# AntennaPCB_EXTV1.net
KiCad netlist of a schematic drawn in EAGLE
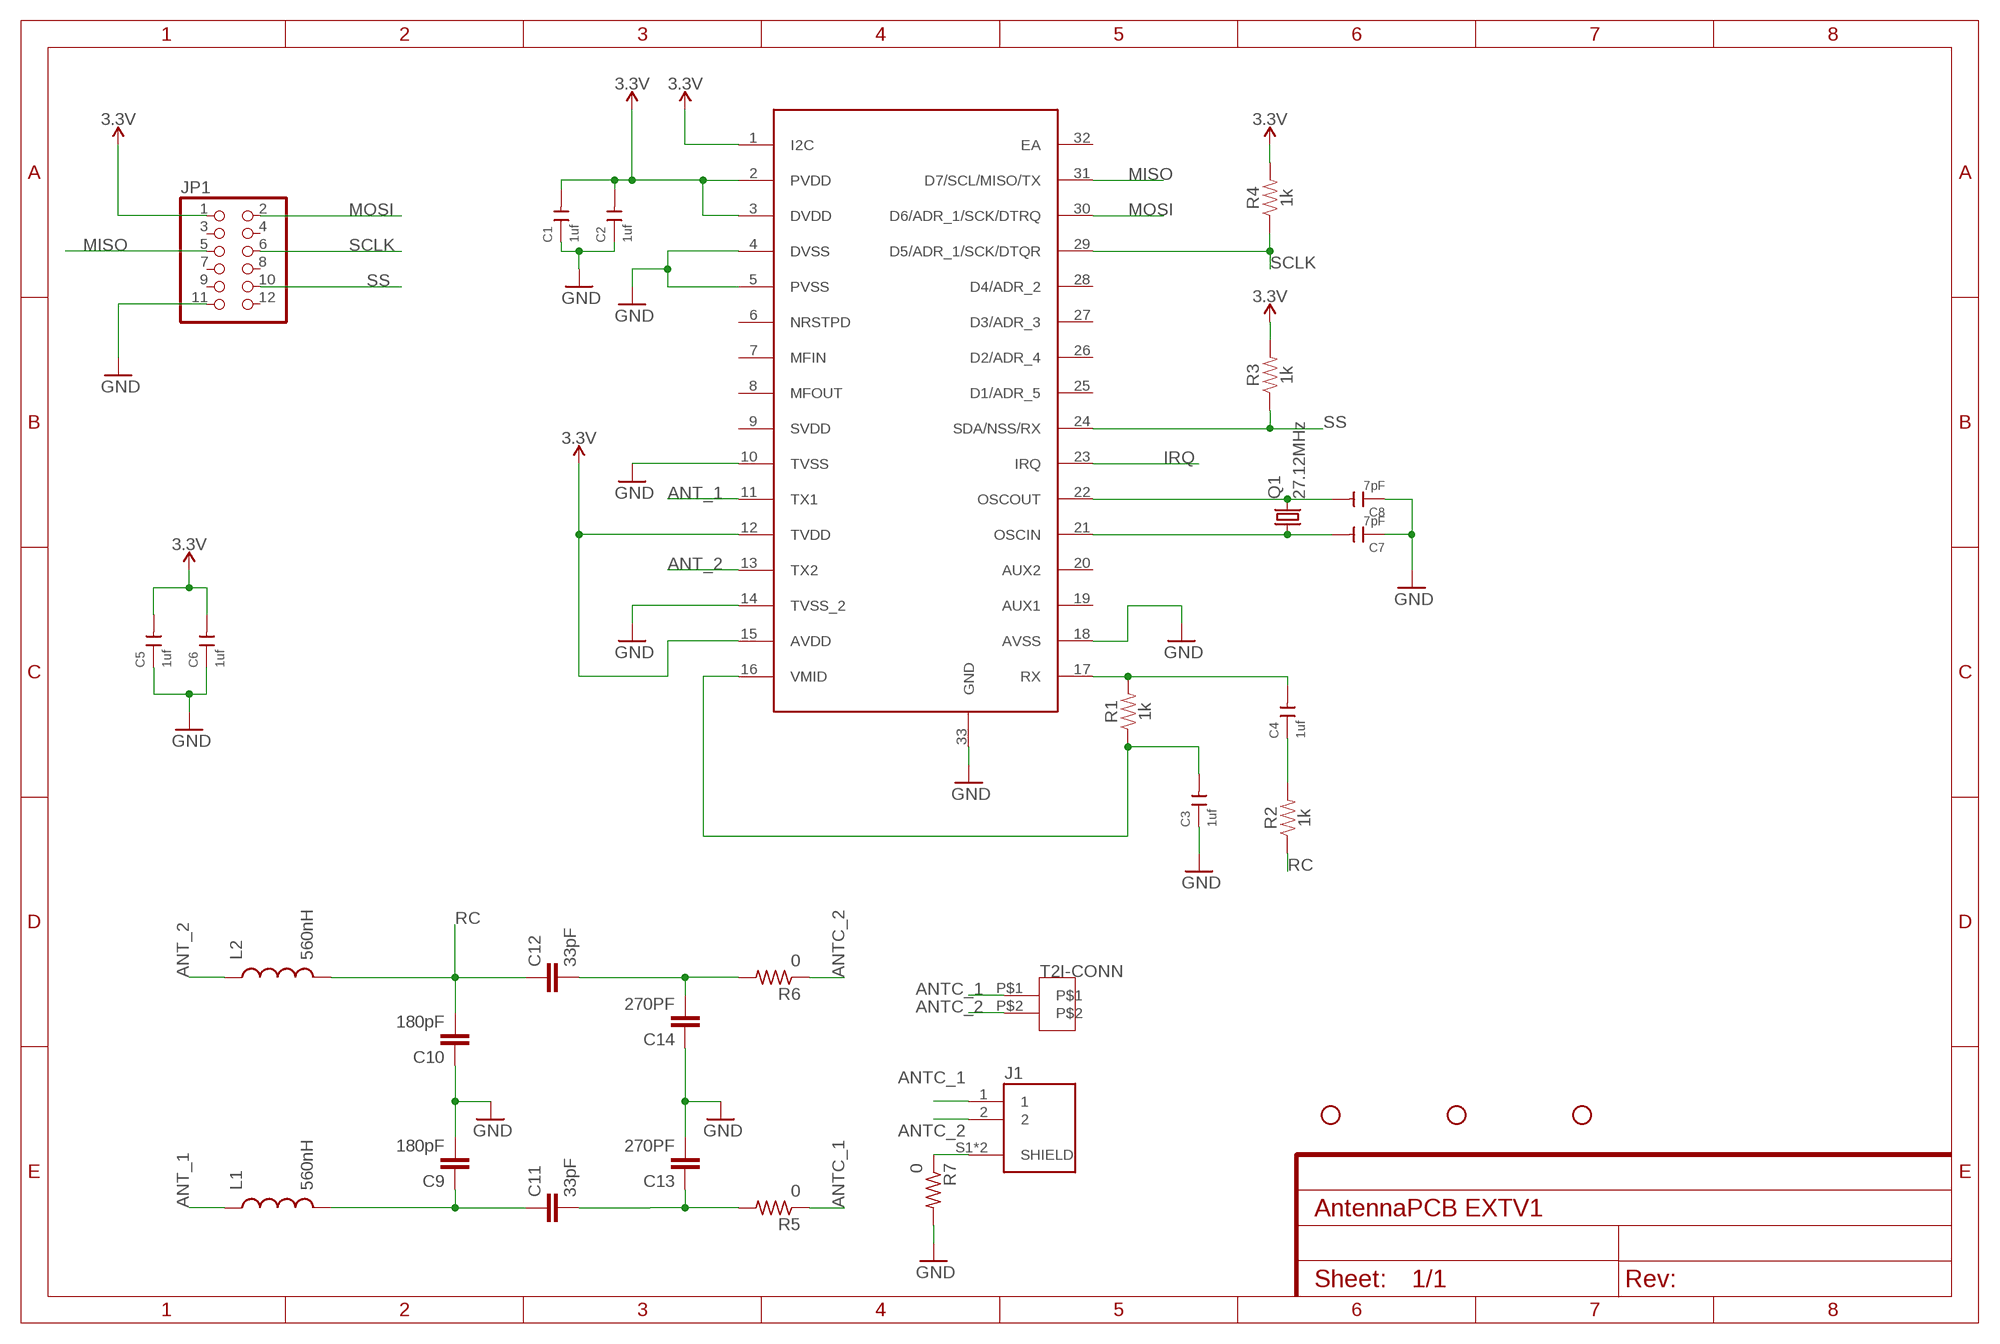
[diagram p0: schematic, sheet 1]

(export (version "E")
  (design (tool "Eeschema 10.0.6"))
  (components
    (comp (ref "C1")
      (value "1uf")
      (footprint "eagle-import:C0603")
      (fields (field (name "MPN") "CC0603KRX7R8BB105"))
      (libsource (lib "eagle-import") (part "CERAMIC-1UF-25V-10%-X7R(0603)"))
    )
    (comp (ref "C2")
      (value "1uf")
      (footprint "eagle-import:C0603")
      (fields (field (name "MPN") "CC0603KRX7R8BB105"))
      (libsource (lib "eagle-import") (part "CERAMIC-1UF-25V-10%-X7R(0603)"))
    )
    (comp (ref "C3")
      (value "1uf")
      (footprint "eagle-import:C0603")
      (fields (field (name "MPN") "CC0603KRX7R8BB105"))
      (libsource (lib "eagle-import") (part "CERAMIC-1UF-25V-10%-X7R(0603)"))
    )
    (comp (ref "C4")
      (value "1uf")
      (footprint "eagle-import:C0603")
      (fields (field (name "MPN") "CC0603KRX7R8BB105"))
      (libsource (lib "eagle-import") (part "CERAMIC-1UF-25V-10%-X7R(0603)"))
    )
    (comp (ref "C5")
      (value "1uf")
      (footprint "eagle-import:C0603")
      (fields (field (name "MPN") "CC0603KRX7R8BB105"))
      (libsource (lib "eagle-import") (part "CERAMIC-1UF-25V-10%-X7R(0603)"))
    )
    (comp (ref "C6")
      (value "1uf")
      (footprint "eagle-import:C0603")
      (fields (field (name "MPN") "CC0603KRX7R8BB105"))
      (libsource (lib "eagle-import") (part "CERAMIC-1UF-25V-10%-X7R(0603)"))
    )
    (comp (ref "C7")
      (value "7pF")
      (footprint "eagle-import:C0603")
      (fields (field (name "MPN") "CC0603KRX7R8BB105"))
      (libsource (lib "eagle-import") (part "CERAMIC-1UF-25V-10%-X7R(0603)"))
    )
    (comp (ref "C8")
      (value "7pF")
      (footprint "eagle-import:C0603")
      (fields (field (name "MPN") "CC0603KRX7R8BB105"))
      (libsource (lib "eagle-import") (part "CERAMIC-1UF-25V-10%-X7R(0603)"))
    )
    (comp (ref "C9")
      (value "180pF")
      (footprint "eagle-import:0603")
      (libsource (lib "eagle-import") (part "180PF-0603-50V-5%"))
    )
    (comp (ref "C10")
      (value "180pF")
      (footprint "eagle-import:0603")
      (libsource (lib "eagle-import") (part "180PF-0603-50V-5%"))
    )
    (comp (ref "C11")
      (value "33pF")
      (footprint "eagle-import:0603")
      (libsource (lib "eagle-import") (part "33PF-0603-50V-5%"))
    )
    (comp (ref "C12")
      (value "33pF")
      (footprint "eagle-import:0603")
      (libsource (lib "eagle-import") (part "33PF-0603-50V-5%"))
    )
    (comp (ref "C13")
      (value "270PF")
      (footprint "eagle-import:0603")
      (libsource (lib "eagle-import") (part "270PF-0603-50V-5%"))
    )
    (comp (ref "C14")
      (value "270PF")
      (footprint "eagle-import:0603")
      (libsource (lib "eagle-import") (part "270PF-0603-50V-5%"))
    )
    (comp (ref "H1")
      (value "STAND-OFF")
      (footprint "eagle-import:STAND-OFF")
      (libsource (lib "eagle-import") (part "STAND-OFF"))
    )
    (comp (ref "H2")
      (value "STAND-OFF")
      (footprint "eagle-import:STAND-OFF")
      (libsource (lib "eagle-import") (part "STAND-OFF"))
    )
    (comp (ref "H3")
      (value "STAND-OFF")
      (footprint "eagle-import:STAND-OFF")
      (libsource (lib "eagle-import") (part "STAND-OFF"))
    )
    (comp (ref "J1")
      (value "BM02B-ACHSS-GAN-TF(LF)(SN)")
      (footprint "eagle-import:JST_BM02B-ACHSS-GAN-TF(LF)(SN)")
      (fields (field (name "MF") "JST Sales") (field (name "MP") "BM02B-ACHSS-GAN-TF_LF__SN_"))
      (libsource (lib "eagle-import") (part "BM02B-ACHSS-GAN-TF(LF)(SN)"))
    )
    (comp (ref "JP1")
      (value "PINHD-2X6")
      (footprint "eagle-import:2X06")
      (libsource (lib "eagle-import") (part "PINHD-2X6"))
    )
    (comp (ref "L1")
      (value "560nH")
      (footprint "eagle-import:L0603")
      (libsource (lib "eagle-import") (part "INDUCTOR"))
    )
    (comp (ref "L2")
      (value "560nH")
      (footprint "eagle-import:L0603")
      (libsource (lib "eagle-import") (part "INDUCTOR"))
    )
    (comp (ref "Q1")
      (value "27.12MHz")
      (footprint "eagle-import:HC49_S")
      (libsource (lib "eagle-import") (part "CRYSTALHC49S"))
    )
    (comp (ref "R1")
      (value "1k")
      (footprint "eagle-import:0603")
      (libsource (lib "eagle-import") (part "1KOHM-0603-1/10W-1%"))
    )
    (comp (ref "R2")
      (value "1k")
      (footprint "eagle-import:0603")
      (libsource (lib "eagle-import") (part "1KOHM-0603-1/10W-1%"))
    )
    (comp (ref "R3")
      (value "1k")
      (footprint "eagle-import:0603")
      (libsource (lib "eagle-import") (part "1KOHM-0603-1/10W-1%"))
    )
    (comp (ref "R4")
      (value "1k")
      (footprint "eagle-import:0603")
      (libsource (lib "eagle-import") (part "1KOHM-0603-1/10W-1%"))
    )
    (comp (ref "R5")
      (value "0")
      (footprint "eagle-import:RES_1206")
      (fields
        (field (name "DIGIKEY_PART_NUMBER") "P0.0ETR-ND")
        (field (name "MANUFACTURER") "Panasonic Electronic Components")
        (field (name "MPN") "ERJ-8GEY0R00V")
        (field (name "CREATED_BY") "PCBLayout.com")
      )
      (libsource (lib "eagle-import") (part "ERJ-8GEY0R00V"))
    )
    (comp (ref "R6")
      (value "0")
      (footprint "eagle-import:RES_1206")
      (fields
        (field (name "DIGIKEY_PART_NUMBER") "P0.0ETR-ND")
        (field (name "MANUFACTURER") "Panasonic Electronic Components")
        (field (name "MPN") "ERJ-8GEY0R00V")
        (field (name "CREATED_BY") "PCBLayout.com")
      )
      (libsource (lib "eagle-import") (part "ERJ-8GEY0R00V"))
    )
    (comp (ref "R7")
      (value "0")
      (footprint "eagle-import:RES_1206")
      (fields
        (field (name "DIGIKEY_PART_NUMBER") "P0.0ETR-ND")
        (field (name "MANUFACTURER") "Panasonic Electronic Components")
        (field (name "MPN") "ERJ-8GEY0R00V")
        (field (name "CREATED_BY") "PCBLayout.com")
      )
      (libsource (lib "eagle-import") (part "ERJ-8GEY0R00V"))
    )
    (comp (ref "U$1")
      (value "MFRC522")
      (footprint "eagle-import:HVQFN32")
      (libsource (lib "eagle-import") (part "MFRC522"))
    )
    (comp (ref "U$2")
      (value "T2I-02")
      (footprint "eagle-import:T2I-02")
      (libsource (lib "eagle-import") (part "T2I-02"))
    )
  )
  (nets
    (net (code "1") (name "/ANTC_1") (class "Default")
      (node (ref "J1") (pin "1") (pinfunction "1_1") (pintype "passive"))
      (node (ref "R5") (pin "1") (pinfunction "1_1") (pintype "passive"))
      (node (ref "U$2") (pin "P$1") (pinfunction "P$1_P$1") (pintype "bidirectional"))
    )
    (net (code "2") (name "/ANTC_2") (class "Default")
      (node (ref "J1") (pin "2") (pinfunction "2_2") (pintype "passive"))
      (node (ref "R6") (pin "1") (pinfunction "1_1") (pintype "passive"))
      (node (ref "U$2") (pin "P$2") (pinfunction "P$2_P$2") (pintype "bidirectional"))
    )
    (net (code "3") (name "/ANT_1") (class "Default")
      (node (ref "L1") (pin "1") (pinfunction "1_1") (pintype "passive"))
      (node (ref "U$1") (pin "11") (pinfunction "TX1_11") (pintype "bidirectional"))
    )
    (net (code "4") (name "/ANT_2") (class "Default")
      (node (ref "L2") (pin "1") (pinfunction "1_1") (pintype "passive"))
      (node (ref "U$1") (pin "13") (pinfunction "TX2_13") (pintype "bidirectional"))
    )
    (net (code "5") (name "/IRQ") (class "Default")
      (node (ref "U$1") (pin "23") (pinfunction "IRQ_23") (pintype "bidirectional"))
    )
    (net (code "6") (name "/MISO") (class "Default")
      (node (ref "JP1") (pin "5") (pinfunction "5_5") (pintype "passive"))
      (node (ref "U$1") (pin "31") (pinfunction "D7/SCL/MISO/TX_31") (pintype "bidirectional"))
    )
    (net (code "7") (name "/MOSI") (class "Default")
      (node (ref "JP1") (pin "2") (pinfunction "2_2") (pintype "passive"))
      (node (ref "U$1") (pin "30") (pinfunction "D6/ADR_1/SCK/DTRQ_30") (pintype "bidirectional"))
    )
    (net (code "8") (name "/RC") (class "Default")
      (node (ref "C10") (pin "2") (pinfunction "2_2") (pintype "passive"))
      (node (ref "C12") (pin "1") (pinfunction "1_1") (pintype "passive"))
      (node (ref "L2") (pin "2") (pinfunction "2_2") (pintype "passive"))
      (node (ref "R2") (pin "1") (pinfunction "1_1") (pintype "passive"))
    )
    (net (code "9") (name "/SCLK") (class "Default")
      (node (ref "JP1") (pin "6") (pinfunction "6_6") (pintype "passive"))
      (node (ref "R4") (pin "1") (pinfunction "1_1") (pintype "passive"))
      (node (ref "U$1") (pin "29") (pinfunction "D5/ADR_1/SCK/DTQR_29") (pintype "bidirectional"))
    )
    (net (code "10") (name "/SS") (class "Default")
      (node (ref "JP1") (pin "10") (pinfunction "10_10") (pintype "passive"))
      (node (ref "R3") (pin "1") (pinfunction "1_1") (pintype "passive"))
      (node (ref "U$1") (pin "24") (pinfunction "SDA/NSS/RX_24") (pintype "bidirectional"))
    )
    (net (code "11") (name "3.3V") (class "Default")
      (node (ref "C1") (pin "2") (pinfunction "2_2") (pintype "passive"))
      (node (ref "C2") (pin "2") (pinfunction "2_2") (pintype "passive"))
      (node (ref "C5") (pin "2") (pinfunction "2_2") (pintype "passive"))
      (node (ref "C6") (pin "2") (pinfunction "2_2") (pintype "passive"))
      (node (ref "JP1") (pin "1") (pinfunction "1_1") (pintype "passive"))
      (node (ref "R3") (pin "2") (pinfunction "2_2") (pintype "passive"))
      (node (ref "R4") (pin "2") (pinfunction "2_2") (pintype "passive"))
      (node (ref "U$1") (pin "1") (pinfunction "I2C_1") (pintype "bidirectional"))
      (node (ref "U$1") (pin "12") (pinfunction "TVDD_12") (pintype "bidirectional"))
      (node (ref "U$1") (pin "15") (pinfunction "AVDD_15") (pintype "bidirectional"))
      (node (ref "U$1") (pin "2") (pinfunction "PVDD_2") (pintype "bidirectional"))
      (node (ref "U$1") (pin "3") (pinfunction "DVDD_3") (pintype "bidirectional"))
    )
    (net (code "12") (name "GND") (class "Default")
      (node (ref "C1") (pin "1") (pinfunction "1_1") (pintype "passive"))
      (node (ref "C10") (pin "1") (pinfunction "1_1") (pintype "passive"))
      (node (ref "C13") (pin "2") (pinfunction "2_2") (pintype "passive"))
      (node (ref "C14") (pin "1") (pinfunction "1_1") (pintype "passive"))
      (node (ref "C2") (pin "1") (pinfunction "1_1") (pintype "passive"))
      (node (ref "C3") (pin "1") (pinfunction "1_1") (pintype "passive"))
      (node (ref "C5") (pin "1") (pinfunction "1_1") (pintype "passive"))
      (node (ref "C6") (pin "1") (pinfunction "1_1") (pintype "passive"))
      (node (ref "C7") (pin "1") (pinfunction "1_1") (pintype "passive"))
      (node (ref "C8") (pin "1") (pinfunction "1_1") (pintype "passive"))
      (node (ref "C9") (pin "2") (pinfunction "2_2") (pintype "passive"))
      (node (ref "JP1") (pin "11") (pinfunction "11_11") (pintype "passive"))
      (node (ref "R7") (pin "2") (pinfunction "2_2") (pintype "passive"))
      (node (ref "U$1") (pin "10") (pinfunction "TVSS_10") (pintype "bidirectional"))
      (node (ref "U$1") (pin "14") (pinfunction "TVSS_2_14") (pintype "bidirectional"))
      (node (ref "U$1") (pin "18") (pinfunction "AVSS_18") (pintype "bidirectional"))
      (node (ref "U$1") (pin "33") (pinfunction "GND_33") (pintype "bidirectional"))
      (node (ref "U$1") (pin "4") (pinfunction "DVSS_4") (pintype "bidirectional"))
      (node (ref "U$1") (pin "5") (pinfunction "PVSS_5") (pintype "bidirectional"))
    )
    (net (code "13") (name "Net-(C4-Pad1)") (class "Default")
      (node (ref "C4") (pin "1") (pinfunction "1_1") (pintype "passive"))
      (node (ref "R2") (pin "2") (pinfunction "2_2") (pintype "passive"))
    )
    (net (code "14") (name "Net-(C11-Pad1)") (class "Default")
      (node (ref "C11") (pin "1") (pinfunction "1_1") (pintype "passive"))
      (node (ref "C9") (pin "1") (pinfunction "1_1") (pintype "passive"))
      (node (ref "L1") (pin "2") (pinfunction "2_2") (pintype "passive"))
    )
    (net (code "15") (name "Net-(C11-Pad2)") (class "Default")
      (node (ref "C11") (pin "2") (pinfunction "2_2") (pintype "passive"))
      (node (ref "C13") (pin "1") (pinfunction "1_1") (pintype "passive"))
      (node (ref "R5") (pin "2") (pinfunction "2_2") (pintype "passive"))
    )
    (net (code "16") (name "Net-(C12-Pad2)") (class "Default")
      (node (ref "C12") (pin "2") (pinfunction "2_2") (pintype "passive"))
      (node (ref "C14") (pin "2") (pinfunction "2_2") (pintype "passive"))
      (node (ref "R6") (pin "2") (pinfunction "2_2") (pintype "passive"))
    )
    (net (code "17") (name "Net-(J1-SHIELD-PadS1)") (class "Default")
      (node (ref "J1") (pin "S1") (pinfunction "SHIELD_S1") (pintype "passive"))
      (node (ref "J1") (pin "S2") (pinfunction "SHIELD_S2") (pintype "passive"))
      (node (ref "R7") (pin "1") (pinfunction "1_1") (pintype "passive"))
    )
    (net (code "18") (name "Net-(U$1-OSCIN)") (class "Default")
      (node (ref "C7") (pin "2") (pinfunction "2_2") (pintype "passive"))
      (node (ref "Q1") (pin "1") (pinfunction "1_1") (pintype "passive"))
      (node (ref "U$1") (pin "21") (pinfunction "OSCIN_21") (pintype "bidirectional"))
    )
    (net (code "19") (name "Net-(U$1-OSCOUT)") (class "Default")
      (node (ref "C8") (pin "2") (pinfunction "2_2") (pintype "passive"))
      (node (ref "Q1") (pin "2") (pinfunction "2_2") (pintype "passive"))
      (node (ref "U$1") (pin "22") (pinfunction "OSCOUT_22") (pintype "bidirectional"))
    )
    (net (code "20") (name "Net-(U$1-RX)") (class "Default")
      (node (ref "C4") (pin "2") (pinfunction "2_2") (pintype "passive"))
      (node (ref "R1") (pin "2") (pinfunction "2_2") (pintype "passive"))
      (node (ref "U$1") (pin "17") (pinfunction "RX_17") (pintype "bidirectional"))
    )
    (net (code "21") (name "Net-(U$1-VMID)") (class "Default")
      (node (ref "C3") (pin "2") (pinfunction "2_2") (pintype "passive"))
      (node (ref "R1") (pin "1") (pinfunction "1_1") (pintype "passive"))
      (node (ref "U$1") (pin "16") (pinfunction "VMID_16") (pintype "bidirectional"))
    )
    (net (code "22") (name "unconnected-(JP1-Pad3)") (class "Default")
      (node (ref "JP1") (pin "3") (pinfunction "3_3") (pintype "passive"))
    )
    (net (code "23") (name "unconnected-(JP1-Pad4)") (class "Default")
      (node (ref "JP1") (pin "4") (pinfunction "4_4") (pintype "passive"))
    )
    (net (code "24") (name "unconnected-(JP1-Pad7)") (class "Default")
      (node (ref "JP1") (pin "7") (pinfunction "7_7") (pintype "passive"))
    )
    (net (code "25") (name "unconnected-(JP1-Pad8)") (class "Default")
      (node (ref "JP1") (pin "8") (pinfunction "8_8") (pintype "passive"))
    )
    (net (code "26") (name "unconnected-(JP1-Pad9)") (class "Default")
      (node (ref "JP1") (pin "9") (pinfunction "9_9") (pintype "passive"))
    )
    (net (code "27") (name "unconnected-(JP1-Pad12)") (class "Default")
      (node (ref "JP1") (pin "12") (pinfunction "12_12") (pintype "passive"))
    )
    (net (code "28") (name "unconnected-(U$1-AUX1-Pad19)") (class "Default")
      (node (ref "U$1") (pin "19") (pinfunction "AUX1_19") (pintype "bidirectional"))
    )
    (net (code "29") (name "unconnected-(U$1-AUX2-Pad20)") (class "Default")
      (node (ref "U$1") (pin "20") (pinfunction "AUX2_20") (pintype "bidirectional"))
    )
    (net (code "30") (name "unconnected-(U$1-D1{slash}ADR_5-Pad25)") (class "Default")
      (node (ref "U$1") (pin "25") (pinfunction "D1/ADR_5_25") (pintype "bidirectional"))
    )
    (net (code "31") (name "unconnected-(U$1-D2{slash}ADR_4-Pad26)") (class "Default")
      (node (ref "U$1") (pin "26") (pinfunction "D2/ADR_4_26") (pintype "bidirectional"))
    )
    (net (code "32") (name "unconnected-(U$1-D3{slash}ADR_3-Pad27)") (class "Default")
      (node (ref "U$1") (pin "27") (pinfunction "D3/ADR_3_27") (pintype "bidirectional"))
    )
    (net (code "33") (name "unconnected-(U$1-D4{slash}ADR_2-Pad28)") (class "Default")
      (node (ref "U$1") (pin "28") (pinfunction "D4/ADR_2_28") (pintype "bidirectional"))
    )
    (net (code "34") (name "unconnected-(U$1-EA-Pad32)") (class "Default")
      (node (ref "U$1") (pin "32") (pinfunction "EA_32") (pintype "bidirectional"))
    )
    (net (code "35") (name "unconnected-(U$1-MFIN-Pad7)") (class "Default")
      (node (ref "U$1") (pin "7") (pinfunction "MFIN_7") (pintype "bidirectional"))
    )
    (net (code "36") (name "unconnected-(U$1-MFOUT-Pad8)") (class "Default")
      (node (ref "U$1") (pin "8") (pinfunction "MFOUT_8") (pintype "bidirectional"))
    )
    (net (code "37") (name "unconnected-(U$1-NRSTPD-Pad6)") (class "Default")
      (node (ref "U$1") (pin "6") (pinfunction "NRSTPD_6") (pintype "bidirectional"))
    )
    (net (code "38") (name "unconnected-(U$1-SVDD-Pad9)") (class "Default")
      (node (ref "U$1") (pin "9") (pinfunction "SVDD_9") (pintype "bidirectional"))
    )
  )
)
